# Flying5.net
KiCad netlist of a schematic drawn in EAGLE
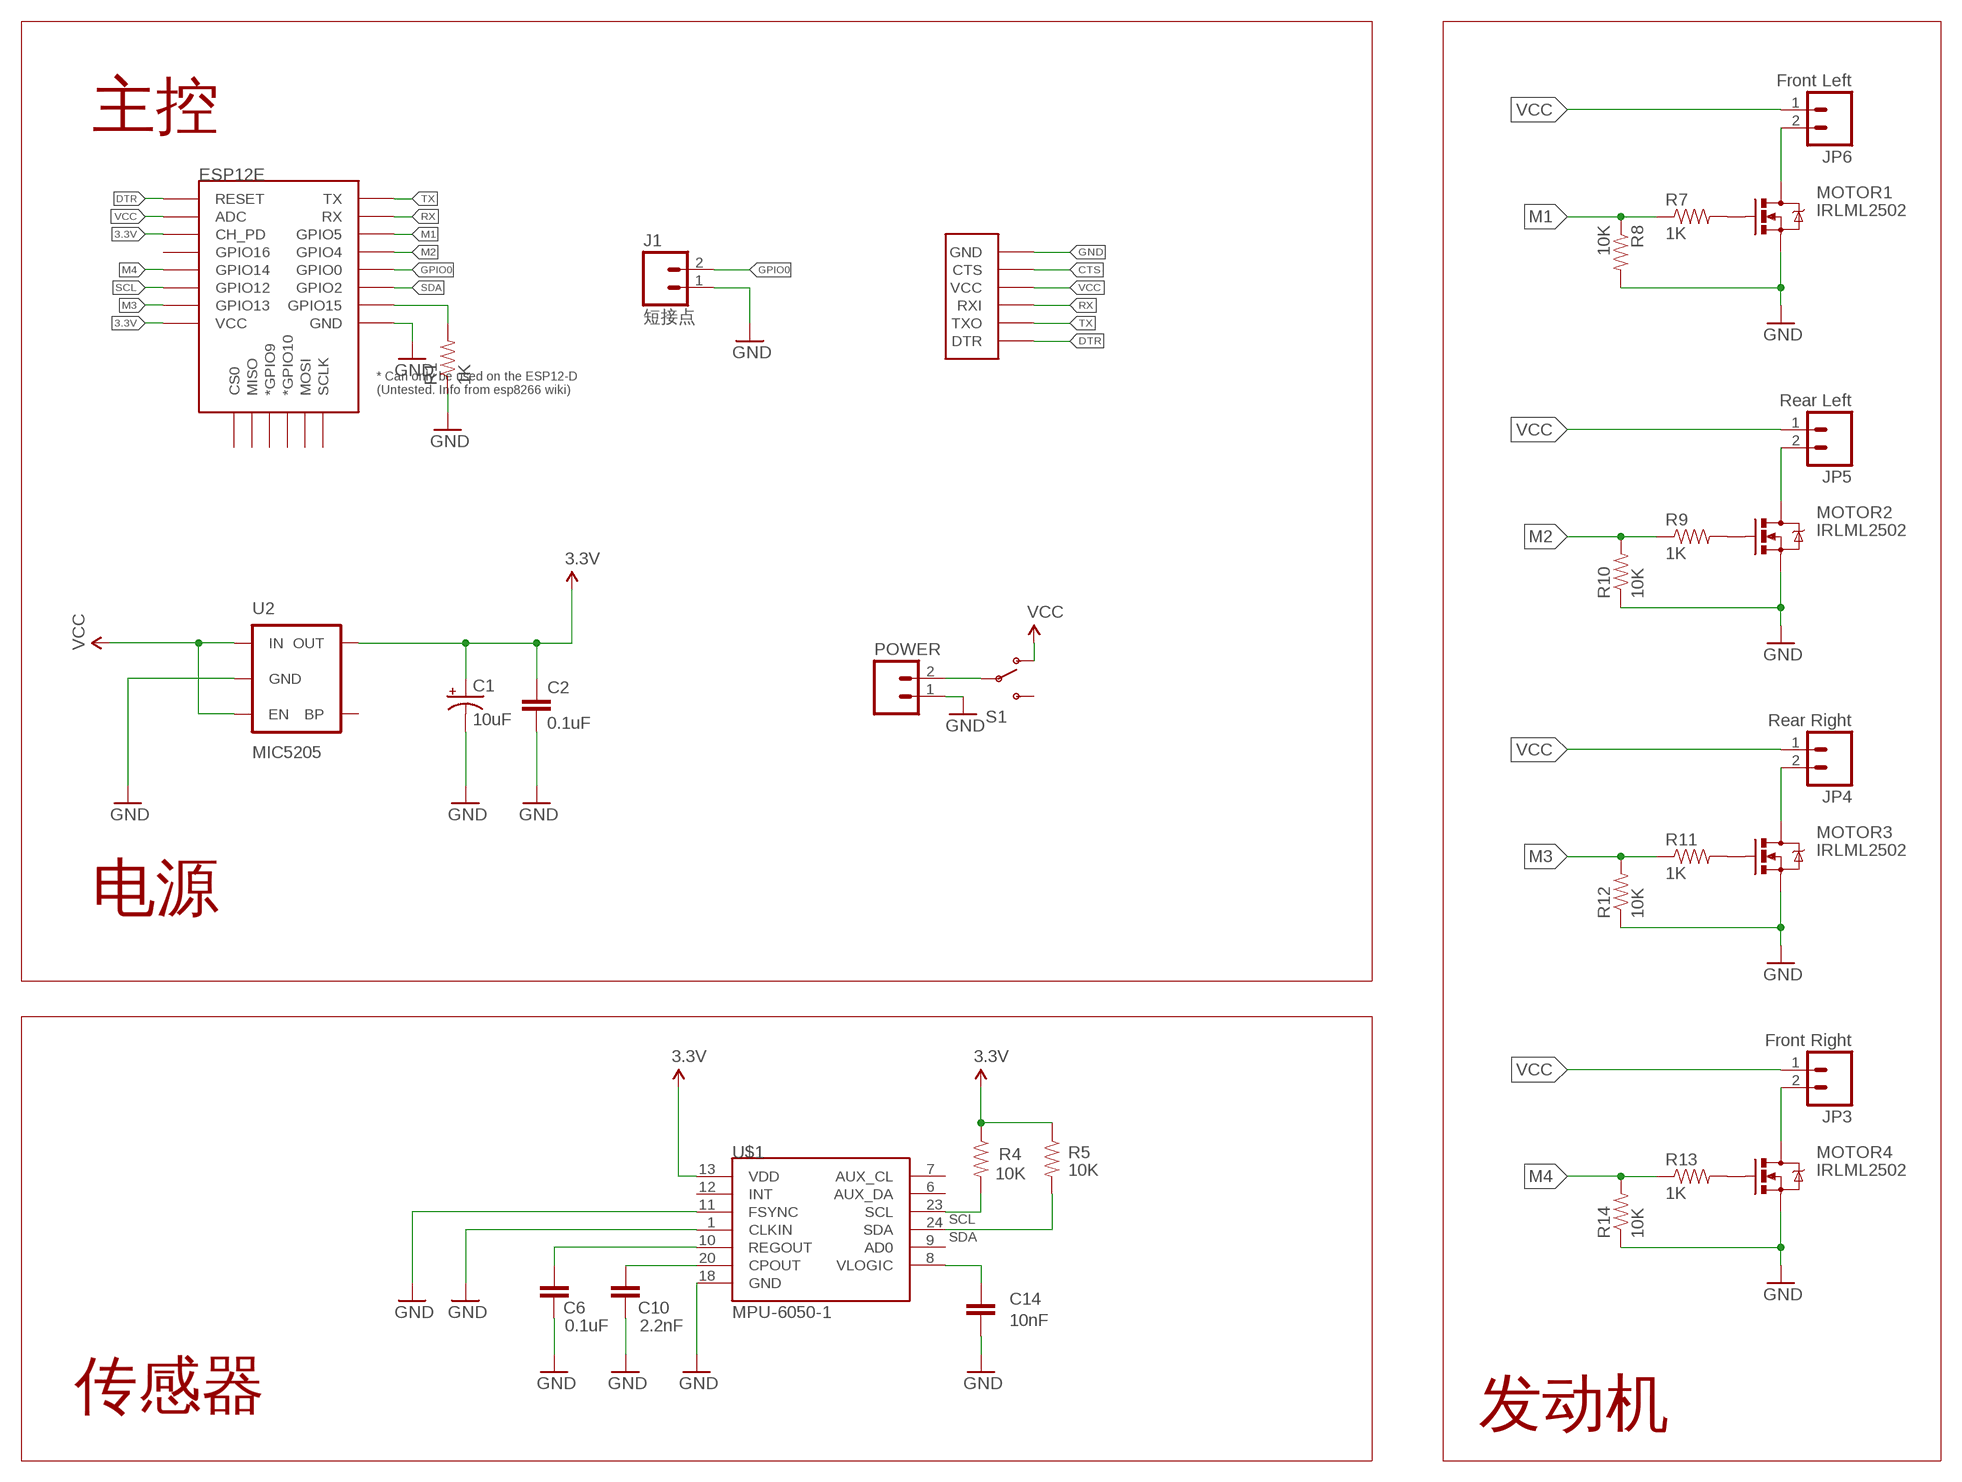
[diagram p0: schematic, sheet 1]

(export (version "E")
  (design (tool "Eeschema 10.0.6"))
  (components
    (comp (ref "C1")
      (value "10uF")
      (footprint "eagle-import:EIA3216")
      (libsource (lib "eagle-import") (part "CAP_POL1206"))
    )
    (comp (ref "C2")
      (value "0.1uF")
      (footprint "eagle-import:0402-CAP")
      (libsource (lib "eagle-import") (part "CAP0402-CAP"))
    )
    (comp (ref "C6")
      (value "0.1uF")
      (footprint "eagle-import:0402-CAP")
      (libsource (lib "eagle-import") (part "CAP0402-CAP"))
    )
    (comp (ref "C10")
      (value "2.2nF")
      (footprint "eagle-import:0402-CAP")
      (libsource (lib "eagle-import") (part "CAP0402-CAP"))
    )
    (comp (ref "C14")
      (value "10nF")
      (footprint "eagle-import:0402-CAP")
      (libsource (lib "eagle-import") (part "CAP0402-CAP"))
    )
    (comp (ref "ESP12E")
      (value "ESP12ESMD")
      (footprint "eagle-import:ESP12E-SMD")
      (libsource (lib "eagle-import") (part "ESP12ESMD"))
    )
    (comp (ref "FTDI")
      (value "FTDI_DEVICE")
      (footprint "eagle-import:FTDI_DEVICE_SIDE")
      (libsource (lib "eagle-import") (part "FTDI_DEVICE"))
    )
    (comp (ref "J1")
      (value "短接点")
      (footprint "eagle-import:1X02")
      (libsource (lib "eagle-import") (part "M02PTH"))
    )
    (comp (ref "JP3")
      (value "Front Right")
      (footprint "eagle-import:1X02_LONGPADS")
      (libsource (lib "eagle-import") (part "M02PTH3"))
    )
    (comp (ref "JP4")
      (value "Rear Right")
      (footprint "eagle-import:1X02_LONGPADS")
      (libsource (lib "eagle-import") (part "M02PTH3"))
    )
    (comp (ref "JP5")
      (value "Rear Left")
      (footprint "eagle-import:1X02_LONGPADS")
      (libsource (lib "eagle-import") (part "M02PTH3"))
    )
    (comp (ref "JP6")
      (value "Front Left")
      (footprint "eagle-import:1X02_LONGPADS")
      (libsource (lib "eagle-import") (part "M02PTH3"))
    )
    (comp (ref "MOTOR1")
      (value "IRLML2502")
      (footprint "eagle-import:SOT23")
      (libsource (lib "eagle-import") (part "MOSFET-NCHANNELBSS138"))
    )
    (comp (ref "MOTOR2")
      (value "IRLML2502")
      (footprint "eagle-import:SOT23")
      (libsource (lib "eagle-import") (part "MOSFET-NCHANNELBSS138"))
    )
    (comp (ref "MOTOR3")
      (value "IRLML2502")
      (footprint "eagle-import:SOT23")
      (libsource (lib "eagle-import") (part "MOSFET-NCHANNELBSS138"))
    )
    (comp (ref "MOTOR4")
      (value "IRLML2502")
      (footprint "eagle-import:SOT23")
      (libsource (lib "eagle-import") (part "MOSFET-NCHANNELBSS138"))
    )
    (comp (ref "POWER")
      (value "M02PTH")
      (footprint "eagle-import:1X02")
      (libsource (lib "eagle-import") (part "M02PTH"))
    )
    (comp (ref "R1")
      (value "1K")
      (footprint "eagle-import:0402-RES")
      (libsource (lib "eagle-import") (part "RESISTOR0402-RES"))
    )
    (comp (ref "R4")
      (value "10K")
      (footprint "eagle-import:0402-RES")
      (libsource (lib "eagle-import") (part "RESISTOR0402-RES"))
    )
    (comp (ref "R5")
      (value "10K")
      (footprint "eagle-import:0402-RES")
      (libsource (lib "eagle-import") (part "RESISTOR0402-RES"))
    )
    (comp (ref "R7")
      (value "1K")
      (footprint "eagle-import:0402-RES")
      (libsource (lib "eagle-import") (part "RESISTOR0402-RES"))
    )
    (comp (ref "R8")
      (value "10K")
      (footprint "eagle-import:0402-RES")
      (libsource (lib "eagle-import") (part "RESISTOR0402-RES"))
    )
    (comp (ref "R9")
      (value "1K")
      (footprint "eagle-import:0402-RES")
      (libsource (lib "eagle-import") (part "RESISTOR0402-RES"))
    )
    (comp (ref "R10")
      (value "10K")
      (footprint "eagle-import:0402-RES")
      (libsource (lib "eagle-import") (part "RESISTOR0402-RES"))
    )
    (comp (ref "R11")
      (value "1K")
      (footprint "eagle-import:0402-RES")
      (libsource (lib "eagle-import") (part "RESISTOR0402-RES"))
    )
    (comp (ref "R12")
      (value "10K")
      (footprint "eagle-import:0402-RES")
      (libsource (lib "eagle-import") (part "RESISTOR0402-RES"))
    )
    (comp (ref "R13")
      (value "1K")
      (footprint "eagle-import:0402-RES")
      (libsource (lib "eagle-import") (part "RESISTOR0402-RES"))
    )
    (comp (ref "R14")
      (value "10K")
      (footprint "eagle-import:0402-RES")
      (libsource (lib "eagle-import") (part "RESISTOR0402-RES"))
    )
    (comp (ref "S1")
      (value "SWITCH-SPDT-SMD-A")
      (footprint "eagle-import:SWITCH-SPST-SMD-A")
      (libsource (lib "eagle-import") (part "SWITCH-SPDT-SMD-A"))
    )
    (comp (ref "U$1")
      (value "MPU-6050-1")
      (footprint "eagle-import:QFN-24-4MM2")
      (libsource (lib "eagle-import") (part "MPU-6050-1"))
    )
    (comp (ref "U2")
      (value "MIC5205")
      (footprint "eagle-import:SOT23-5")
      (libsource (lib "eagle-import") (part "MIC52055V"))
    )
  )
  (nets
    (net (code "1") (name "3.3V") (class "Default")
      (node (ref "C1") (pin "A") (pinfunction "+_A") (pintype "passive"))
      (node (ref "C2") (pin "1") (pinfunction "1_1") (pintype "passive"))
      (node (ref "ESP12E") (pin "CH_PD") (pinfunction "CH_PD_CH_PD") (pintype "bidirectional"))
      (node (ref "ESP12E") (pin "VCC") (pinfunction "VCC_VCC") (pintype "bidirectional"))
      (node (ref "R4") (pin "1") (pinfunction "1_1") (pintype "passive"))
      (node (ref "R5") (pin "1") (pinfunction "1_1") (pintype "passive"))
      (node (ref "U$1") (pin "13") (pinfunction "VDD_13") (pintype "bidirectional"))
      (node (ref "U2") (pin "5") (pinfunction "OUT_5") (pintype "passive"))
    )
    (net (code "2") (name "CTS") (class "Default")
      (node (ref "FTDI") (pin "P$5") (pinfunction "CTS_P$5") (pintype "bidirectional"))
    )
    (net (code "3") (name "DTR") (class "Default")
      (node (ref "ESP12E") (pin "RESET") (pinfunction "RESET_RESET") (pintype "bidirectional"))
      (node (ref "FTDI") (pin "P$1") (pinfunction "DTR_P$1") (pintype "bidirectional"))
    )
    (net (code "4") (name "GND") (class "Default")
      (node (ref "C1") (pin "C") (pinfunction "-_C") (pintype "passive"))
      (node (ref "C10") (pin "1") (pinfunction "1_1") (pintype "passive"))
      (node (ref "C14") (pin "1") (pinfunction "1_1") (pintype "passive"))
      (node (ref "C2") (pin "2") (pinfunction "2_2") (pintype "passive"))
      (node (ref "C6") (pin "1") (pinfunction "1_1") (pintype "passive"))
      (node (ref "ESP12E") (pin "GND") (pinfunction "GND_GND") (pintype "bidirectional"))
      (node (ref "FTDI") (pin "P$6") (pinfunction "GND_P$6") (pintype "bidirectional"))
      (node (ref "J1") (pin "1") (pinfunction "1_1") (pintype "passive"))
      (node (ref "MOTOR1") (pin "2") (pinfunction "S_2") (pintype "passive"))
      (node (ref "MOTOR2") (pin "2") (pinfunction "S_2") (pintype "passive"))
      (node (ref "MOTOR3") (pin "2") (pinfunction "S_2") (pintype "passive"))
      (node (ref "MOTOR4") (pin "2") (pinfunction "S_2") (pintype "passive"))
      (node (ref "POWER") (pin "1") (pinfunction "1_1") (pintype "passive"))
      (node (ref "R1") (pin "1") (pinfunction "1_1") (pintype "passive"))
      (node (ref "R10") (pin "1") (pinfunction "1_1") (pintype "passive"))
      (node (ref "R12") (pin "1") (pinfunction "1_1") (pintype "passive"))
      (node (ref "R14") (pin "1") (pinfunction "1_1") (pintype "passive"))
      (node (ref "R8") (pin "2") (pinfunction "2_2") (pintype "passive"))
      (node (ref "U$1") (pin "1") (pinfunction "CLKIN_1") (pintype "bidirectional"))
      (node (ref "U$1") (pin "11") (pinfunction "FSYNC_11") (pintype "bidirectional"))
      (node (ref "U$1") (pin "18") (pinfunction "GND_18") (pintype "bidirectional"))
      (node (ref "U2") (pin "2") (pinfunction "GND_2") (pintype "input"))
    )
    (net (code "5") (name "GPIO0") (class "Default")
      (node (ref "ESP12E") (pin "GPIO0") (pinfunction "GPIO0_GPIO0") (pintype "bidirectional"))
      (node (ref "J1") (pin "2") (pinfunction "2_2") (pintype "passive"))
    )
    (net (code "6") (name "M1") (class "Default")
      (node (ref "ESP12E") (pin "GPIO5") (pinfunction "GPIO5_GPIO5") (pintype "bidirectional"))
      (node (ref "R7") (pin "1") (pinfunction "1_1") (pintype "passive"))
      (node (ref "R8") (pin "1") (pinfunction "1_1") (pintype "passive"))
    )
    (net (code "7") (name "M2") (class "Default")
      (node (ref "ESP12E") (pin "GPIO4") (pinfunction "GPIO4_GPIO4") (pintype "bidirectional"))
      (node (ref "R10") (pin "2") (pinfunction "2_2") (pintype "passive"))
      (node (ref "R9") (pin "1") (pinfunction "1_1") (pintype "passive"))
    )
    (net (code "8") (name "M3") (class "Default")
      (node (ref "ESP12E") (pin "GPIO13") (pinfunction "GPIO13_GPIO13") (pintype "bidirectional"))
      (node (ref "R11") (pin "1") (pinfunction "1_1") (pintype "passive"))
      (node (ref "R12") (pin "2") (pinfunction "2_2") (pintype "passive"))
    )
    (net (code "9") (name "M4") (class "Default")
      (node (ref "ESP12E") (pin "GPIO14") (pinfunction "GPIO14_GPIO14") (pintype "bidirectional"))
      (node (ref "R13") (pin "1") (pinfunction "1_1") (pintype "passive"))
      (node (ref "R14") (pin "2") (pinfunction "2_2") (pintype "passive"))
    )
    (net (code "10") (name "Net-(ESP12E-PadGPIO15)") (class "Default")
      (node (ref "ESP12E") (pin "GPIO15") (pinfunction "GPIO15_GPIO15") (pintype "bidirectional"))
      (node (ref "R1") (pin "2") (pinfunction "2_2") (pintype "passive"))
    )
    (net (code "11") (name "Net-(MOTOR1-D)") (class "Default")
      (node (ref "JP6") (pin "2") (pinfunction "2_2") (pintype "passive"))
      (node (ref "MOTOR1") (pin "3") (pinfunction "D_3") (pintype "passive"))
    )
    (net (code "12") (name "Net-(MOTOR1-G)") (class "Default")
      (node (ref "MOTOR1") (pin "1") (pinfunction "G_1") (pintype "passive"))
      (node (ref "R7") (pin "2") (pinfunction "2_2") (pintype "passive"))
    )
    (net (code "13") (name "Net-(MOTOR2-D)") (class "Default")
      (node (ref "JP5") (pin "2") (pinfunction "2_2") (pintype "passive"))
      (node (ref "MOTOR2") (pin "3") (pinfunction "D_3") (pintype "passive"))
    )
    (net (code "14") (name "Net-(MOTOR2-G)") (class "Default")
      (node (ref "MOTOR2") (pin "1") (pinfunction "G_1") (pintype "passive"))
      (node (ref "R9") (pin "2") (pinfunction "2_2") (pintype "passive"))
    )
    (net (code "15") (name "Net-(MOTOR3-D)") (class "Default")
      (node (ref "JP4") (pin "2") (pinfunction "2_2") (pintype "passive"))
      (node (ref "MOTOR3") (pin "3") (pinfunction "D_3") (pintype "passive"))
    )
    (net (code "16") (name "Net-(MOTOR3-G)") (class "Default")
      (node (ref "MOTOR3") (pin "1") (pinfunction "G_1") (pintype "passive"))
      (node (ref "R11") (pin "2") (pinfunction "2_2") (pintype "passive"))
    )
    (net (code "17") (name "Net-(MOTOR4-D)") (class "Default")
      (node (ref "JP3") (pin "2") (pinfunction "2_2") (pintype "passive"))
      (node (ref "MOTOR4") (pin "3") (pinfunction "D_3") (pintype "passive"))
    )
    (net (code "18") (name "Net-(MOTOR4-G)") (class "Default")
      (node (ref "MOTOR4") (pin "1") (pinfunction "G_1") (pintype "passive"))
      (node (ref "R13") (pin "2") (pinfunction "2_2") (pintype "passive"))
    )
    (net (code "19") (name "Net-(S1-P)") (class "Default")
      (node (ref "POWER") (pin "2") (pinfunction "2_2") (pintype "passive"))
      (node (ref "S1") (pin "2") (pinfunction "P_2") (pintype "passive"))
    )
    (net (code "20") (name "Net-(U$1-CPOUT)") (class "Default")
      (node (ref "C10") (pin "2") (pinfunction "2_2") (pintype "passive"))
      (node (ref "U$1") (pin "20") (pinfunction "CPOUT_20") (pintype "bidirectional"))
    )
    (net (code "21") (name "Net-(U$1-REGOUT)") (class "Default")
      (node (ref "C6") (pin "2") (pinfunction "2_2") (pintype "passive"))
      (node (ref "U$1") (pin "10") (pinfunction "REGOUT_10") (pintype "bidirectional"))
    )
    (net (code "22") (name "Net-(U$1-VLOGIC)") (class "Default")
      (node (ref "C14") (pin "2") (pinfunction "2_2") (pintype "passive"))
      (node (ref "U$1") (pin "8") (pinfunction "VLOGIC_8") (pintype "bidirectional"))
    )
    (net (code "23") (name "RX") (class "Default")
      (node (ref "ESP12E") (pin "RXD0") (pinfunction "RX_RXD0") (pintype "bidirectional"))
      (node (ref "FTDI") (pin "P$3") (pinfunction "RXI_P$3") (pintype "bidirectional"))
    )
    (net (code "24") (name "SCL") (class "Default")
      (node (ref "ESP12E") (pin "GPIO12") (pinfunction "GPIO12_GPIO12") (pintype "bidirectional"))
      (node (ref "R4") (pin "2") (pinfunction "2_2") (pintype "passive"))
      (node (ref "U$1") (pin "23") (pinfunction "SCL_23") (pintype "bidirectional"))
    )
    (net (code "25") (name "SDA") (class "Default")
      (node (ref "ESP12E") (pin "GPIO2") (pinfunction "GPIO2_GPIO2") (pintype "bidirectional"))
      (node (ref "R5") (pin "2") (pinfunction "2_2") (pintype "passive"))
      (node (ref "U$1") (pin "24") (pinfunction "SDA_24") (pintype "bidirectional"))
    )
    (net (code "26") (name "TX") (class "Default")
      (node (ref "ESP12E") (pin "TXD0") (pinfunction "TX_TXD0") (pintype "bidirectional"))
      (node (ref "FTDI") (pin "P$2") (pinfunction "TXO_P$2") (pintype "bidirectional"))
    )
    (net (code "27") (name "VCC") (class "Default")
      (node (ref "ESP12E") (pin "ADC") (pinfunction "ADC_ADC") (pintype "bidirectional"))
      (node (ref "FTDI") (pin "P$4") (pinfunction "VCC_P$4") (pintype "bidirectional"))
      (node (ref "JP3") (pin "1") (pinfunction "1_1") (pintype "passive"))
      (node (ref "JP4") (pin "1") (pinfunction "1_1") (pintype "passive"))
      (node (ref "JP5") (pin "1") (pinfunction "1_1") (pintype "passive"))
      (node (ref "JP6") (pin "1") (pinfunction "1_1") (pintype "passive"))
      (node (ref "S1") (pin "1") (pinfunction "O_1") (pintype "passive"))
      (node (ref "U2") (pin "1") (pinfunction "IN_1") (pintype "input"))
      (node (ref "U2") (pin "3") (pinfunction "EN_3") (pintype "input"))
    )
    (net (code "28") (name "unconnected-(ESP12E-*GPIO9-PadGPIO9)") (class "Default")
      (node (ref "ESP12E") (pin "GPIO9") (pinfunction "*GPIO9_GPIO9") (pintype "bidirectional"))
    )
    (net (code "29") (name "unconnected-(ESP12E-*GPIO10-PadGPIO10)") (class "Default")
      (node (ref "ESP12E") (pin "GPIO10") (pinfunction "*GPIO10_GPIO10") (pintype "bidirectional"))
    )
    (net (code "30") (name "unconnected-(ESP12E-PadCS0)") (class "Default")
      (node (ref "ESP12E") (pin "CS0") (pinfunction "CS0_CS0") (pintype "bidirectional"))
    )
    (net (code "31") (name "unconnected-(ESP12E-PadGPIO16)") (class "Default")
      (node (ref "ESP12E") (pin "GPIO16") (pinfunction "GPIO16_GPIO16") (pintype "bidirectional"))
    )
    (net (code "32") (name "unconnected-(ESP12E-PadMISO)") (class "Default")
      (node (ref "ESP12E") (pin "MISO") (pinfunction "MISO_MISO") (pintype "bidirectional"))
    )
    (net (code "33") (name "unconnected-(ESP12E-PadMOSI)") (class "Default")
      (node (ref "ESP12E") (pin "MOSI") (pinfunction "MOSI_MOSI") (pintype "bidirectional"))
    )
    (net (code "34") (name "unconnected-(ESP12E-PadSCLK)") (class "Default")
      (node (ref "ESP12E") (pin "SCLK") (pinfunction "SCLK_SCLK") (pintype "bidirectional"))
    )
    (net (code "35") (name "unconnected-(S1-S-Pad3)") (class "Default")
      (node (ref "S1") (pin "3") (pinfunction "S_3") (pintype "passive"))
    )
    (net (code "36") (name "unconnected-(U$1-AD0-Pad9)") (class "Default")
      (node (ref "U$1") (pin "9") (pinfunction "AD0_9") (pintype "bidirectional"))
    )
    (net (code "37") (name "unconnected-(U$1-AUX_CL-Pad7)") (class "Default")
      (node (ref "U$1") (pin "7") (pinfunction "AUX_CL_7") (pintype "bidirectional"))
    )
    (net (code "38") (name "unconnected-(U$1-AUX_DA-Pad6)") (class "Default")
      (node (ref "U$1") (pin "6") (pinfunction "AUX_DA_6") (pintype "bidirectional"))
    )
    (net (code "39") (name "unconnected-(U$1-INT-Pad12)") (class "Default")
      (node (ref "U$1") (pin "12") (pinfunction "INT_12") (pintype "bidirectional"))
    )
    (net (code "40") (name "unconnected-(U2-BP-Pad4)") (class "Default")
      (node (ref "U2") (pin "4") (pinfunction "BP_4") (pintype "input"))
    )
  )
)
